# USB.net
KiCad netlist of a schematic drawn in Altium Designer
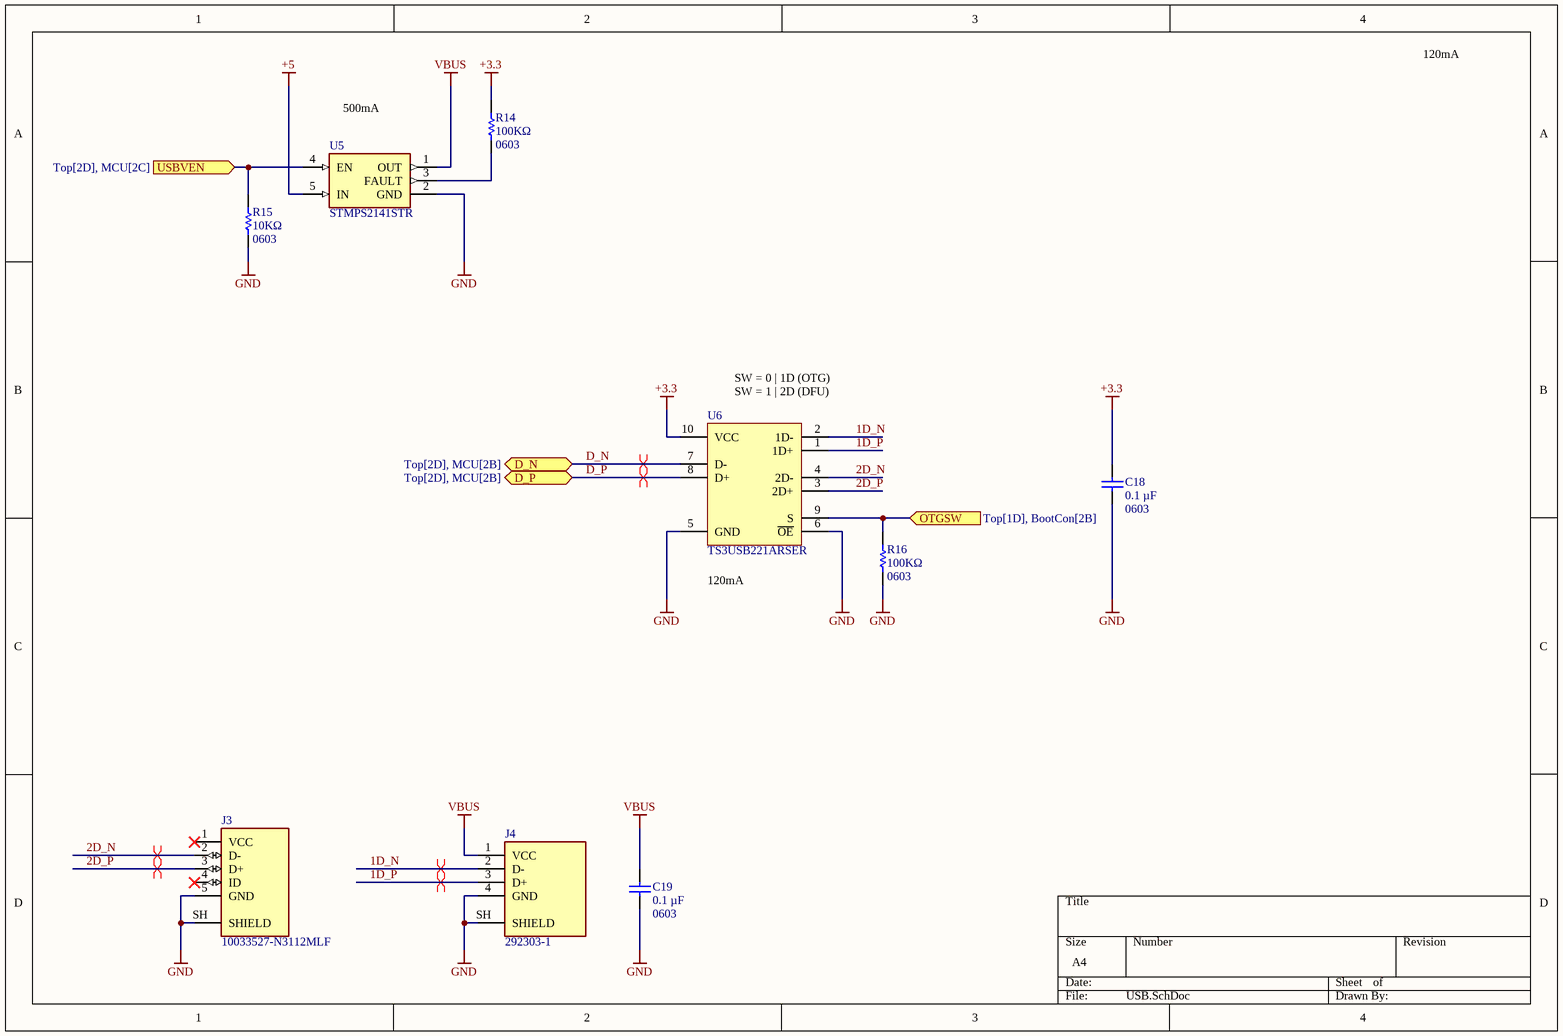
[diagram p0: USB.SchDoc]

(export (version "E")
  (design (tool "Eeschema 10.0.6"))
  (components
    (comp (ref "C18")
      (value "0.1 µF")
      (footprint "0603")
      (description "0.1 µF ±20% 100V Ceramic Capacitor X7R 0603 (1608 Metric)")
      (fields (field (name "CASE") "0603") (field (name "TOLERANCE") "±20%") (field (name "VOLTAGE") "100V"))
      (libsource (lib "Murata Electronics") (part "GRM188R72A104MA35J"))
    )
    (comp (ref "C19")
      (value "0.1 µF")
      (footprint "0603")
      (description "0.1 µF ±20% 100V Ceramic Capacitor X7R 0603 (1608 Metric)")
      (fields (field (name "CASE") "0603") (field (name "TOLERANCE") "±20%") (field (name "VOLTAGE") "100V"))
      (libsource (lib "Murata Electronics") (part "GRM188R72A104MA35J"))
    )
    (comp (ref "J3")
      (value "10033527-N3112MLF")
      (footprint "10033527-N3112MLF")
      (description "USB - mini AB USB 2.0 Receptacle Connector 5 Position Surface Mount, Right Angle")
      (fields (field (name "VOLTAGE") "30V"))
      (libsource (lib "Amphenol ICC (FCI)") (part "10033527-N3112MLF"))
    )
    (comp (ref "J4")
      (value "292303-1")
      (footprint "PCBComponent_1")
      (description "USB-A (USB TYPE-A) USB 2.0 Receptacle Connector 4 Position Through Hole, Right Angle")
      (libsource (lib "TE Connectivity AMP Connectors") (part "292303-1"))
    )
    (comp (ref "R14")
      (value "100KΩ")
      (footprint "0603")
      (description "100 kOhms ±1% 0.1W, 1/10W Chip Resistor 0603 (1608 Metric) Automotive AEC-Q200 Thick Film")
      (fields (field (name "CASE") "0603") (field (name "TOLERANCE") "1%") (field (name "POWER") "0.1W"))
      (libsource (lib "Stackpole Electronics Inc") (part "RMCF0603FG100K"))
    )
    (comp (ref "R15")
      (value "10KΩ")
      (footprint "0603")
      (description "10 kOhms ±1% 0.1W, 1/10W Chip Resistor 0603 (1608 Metric) Automotive AEC-Q200 Thick Film")
      (fields (field (name "CASE") "0603") (field (name "TOLERANCE") "1%") (field (name "POWER") "0.1W"))
      (libsource (lib "Stackpole Electronics Inc") (part "RMCF0603FG10K0"))
    )
    (comp (ref "R16")
      (value "100KΩ")
      (footprint "0603")
      (description "100 kOhms ±1% 0.1W, 1/10W Chip Resistor 0603 (1608 Metric) Automotive AEC-Q200 Thick Film")
      (fields (field (name "CASE") "0603") (field (name "TOLERANCE") "1%") (field (name "POWER") "0.1W"))
      (libsource (lib "Stackpole Electronics Inc") (part "RMCF0603FG100K"))
    )
    (comp (ref "U5")
      (value "STMPS2141STR")
      (footprint "SOT-23-5")
      (description "Power Switch/Driver 1:1 N-Channel 500mA SOT-23-5")
      (libsource (lib "STMicroelectronics") (part "STMPS2141STR"))
    )
    (comp (ref "U6")
      (value "TS3USB221ARSER")
      (footprint "10-UFQFN")
      (description "USB Switch IC 2 Channel 10-UQFN (2.0x1.5)")
      (libsource (lib "Texas Instruments") (part "TS3USB221ARSER"))
    )
  )
  (nets
    (net (code "1") (name "+3.3") (class "Default")
      (node (ref "C18") (pin "2") (pinfunction "2_2") (pintype "passive"))
      (node (ref "R14") (pin "1") (pinfunction "1_1") (pintype "passive"))
      (node (ref "U6") (pin "10") (pinfunction "VCC_10") (pintype "passive"))
    )
    (net (code "2") (name "+5") (class "Default")
      (node (ref "U5") (pin "5") (pinfunction "IN_5") (pintype "input"))
    )
    (net (code "3") (name "/1D_N") (class "Default")
      (node (ref "J4") (pin "2") (pinfunction "D-_2") (pintype "passive"))
      (node (ref "U6") (pin "2") (pinfunction "1D-_2") (pintype "passive"))
    )
    (net (code "4") (name "/1D_P") (class "Default")
      (node (ref "J4") (pin "3") (pinfunction "D+_3") (pintype "passive"))
      (node (ref "U6") (pin "1") (pinfunction "1D+_1") (pintype "passive"))
    )
    (net (code "5") (name "/2D_N") (class "Default")
      (node (ref "J3") (pin "2") (pinfunction "D-_2") (pintype "bidirectional"))
      (node (ref "U6") (pin "4") (pinfunction "2D-_4") (pintype "passive"))
    )
    (net (code "6") (name "/2D_P") (class "Default")
      (node (ref "J3") (pin "3") (pinfunction "D+_3") (pintype "bidirectional"))
      (node (ref "U6") (pin "3") (pinfunction "2D+_3") (pintype "passive"))
    )
    (net (code "7") (name "/D_N") (class "Default")
      (node (ref "U6") (pin "7") (pinfunction "D-_7") (pintype "passive"))
    )
    (net (code "8") (name "/D_P") (class "Default")
      (node (ref "U6") (pin "8") (pinfunction "D+_8") (pintype "passive"))
    )
    (net (code "9") (name "/OTGSW") (class "Default")
      (node (ref "R16") (pin "1") (pinfunction "1_1") (pintype "passive"))
      (node (ref "U6") (pin "9") (pinfunction "S_9") (pintype "passive"))
    )
    (net (code "10") (name "/USBVEN") (class "Default")
      (node (ref "R15") (pin "2") (pinfunction "2_2") (pintype "passive"))
      (node (ref "U5") (pin "4") (pinfunction "EN_4") (pintype "input"))
    )
    (net (code "11") (name "GND") (class "Default")
      (node (ref "C18") (pin "1") (pinfunction "1_1") (pintype "passive"))
      (node (ref "C19") (pin "1") (pinfunction "1_1") (pintype "passive"))
      (node (ref "J3") (pin "5") (pinfunction "GND_5") (pintype "power_in"))
      (node (ref "J3") (pin "SH") (pinfunction "SHIELD_SH") (pintype "passive"))
      (node (ref "J4") (pin "4") (pinfunction "GND_4") (pintype "passive"))
      (node (ref "J4") (pin "SH") (pinfunction "SHIELD_SH") (pintype "passive"))
      (node (ref "R15") (pin "1") (pinfunction "1_1") (pintype "passive"))
      (node (ref "R16") (pin "2") (pinfunction "2_2") (pintype "passive"))
      (node (ref "U5") (pin "2") (pinfunction "GND_2") (pintype "power_in"))
      (node (ref "U6") (pin "5") (pinfunction "GND_5") (pintype "passive"))
      (node (ref "U6") (pin "6") (pinfunction "~{OE}_6") (pintype "passive"))
    )
    (net (code "12") (name "Net-(U5-FAULT)") (class "Default")
      (node (ref "R14") (pin "2") (pinfunction "2_2") (pintype "passive"))
      (node (ref "U5") (pin "3") (pinfunction "FAULT_3") (pintype "output"))
    )
    (net (code "13") (name "VBUS") (class "Default")
      (node (ref "C19") (pin "2") (pinfunction "2_2") (pintype "passive"))
      (node (ref "J4") (pin "1") (pinfunction "VCC_1") (pintype "passive"))
      (node (ref "U5") (pin "1") (pinfunction "OUT_1") (pintype "output"))
    )
    (net (code "14") (name "unconnected-(J3-ID-Pad4)") (class "Default")
      (node (ref "J3") (pin "4") (pinfunction "ID_4") (pintype "bidirectional+no_connect"))
    )
    (net (code "15") (name "unconnected-(J3-VCC-Pad1)") (class "Default")
      (node (ref "J3") (pin "1") (pinfunction "VCC_1") (pintype "power_in+no_connect"))
    )
  )
)
